# RTC-Module.net
KiCad netlist of a schematic drawn in EAGLE
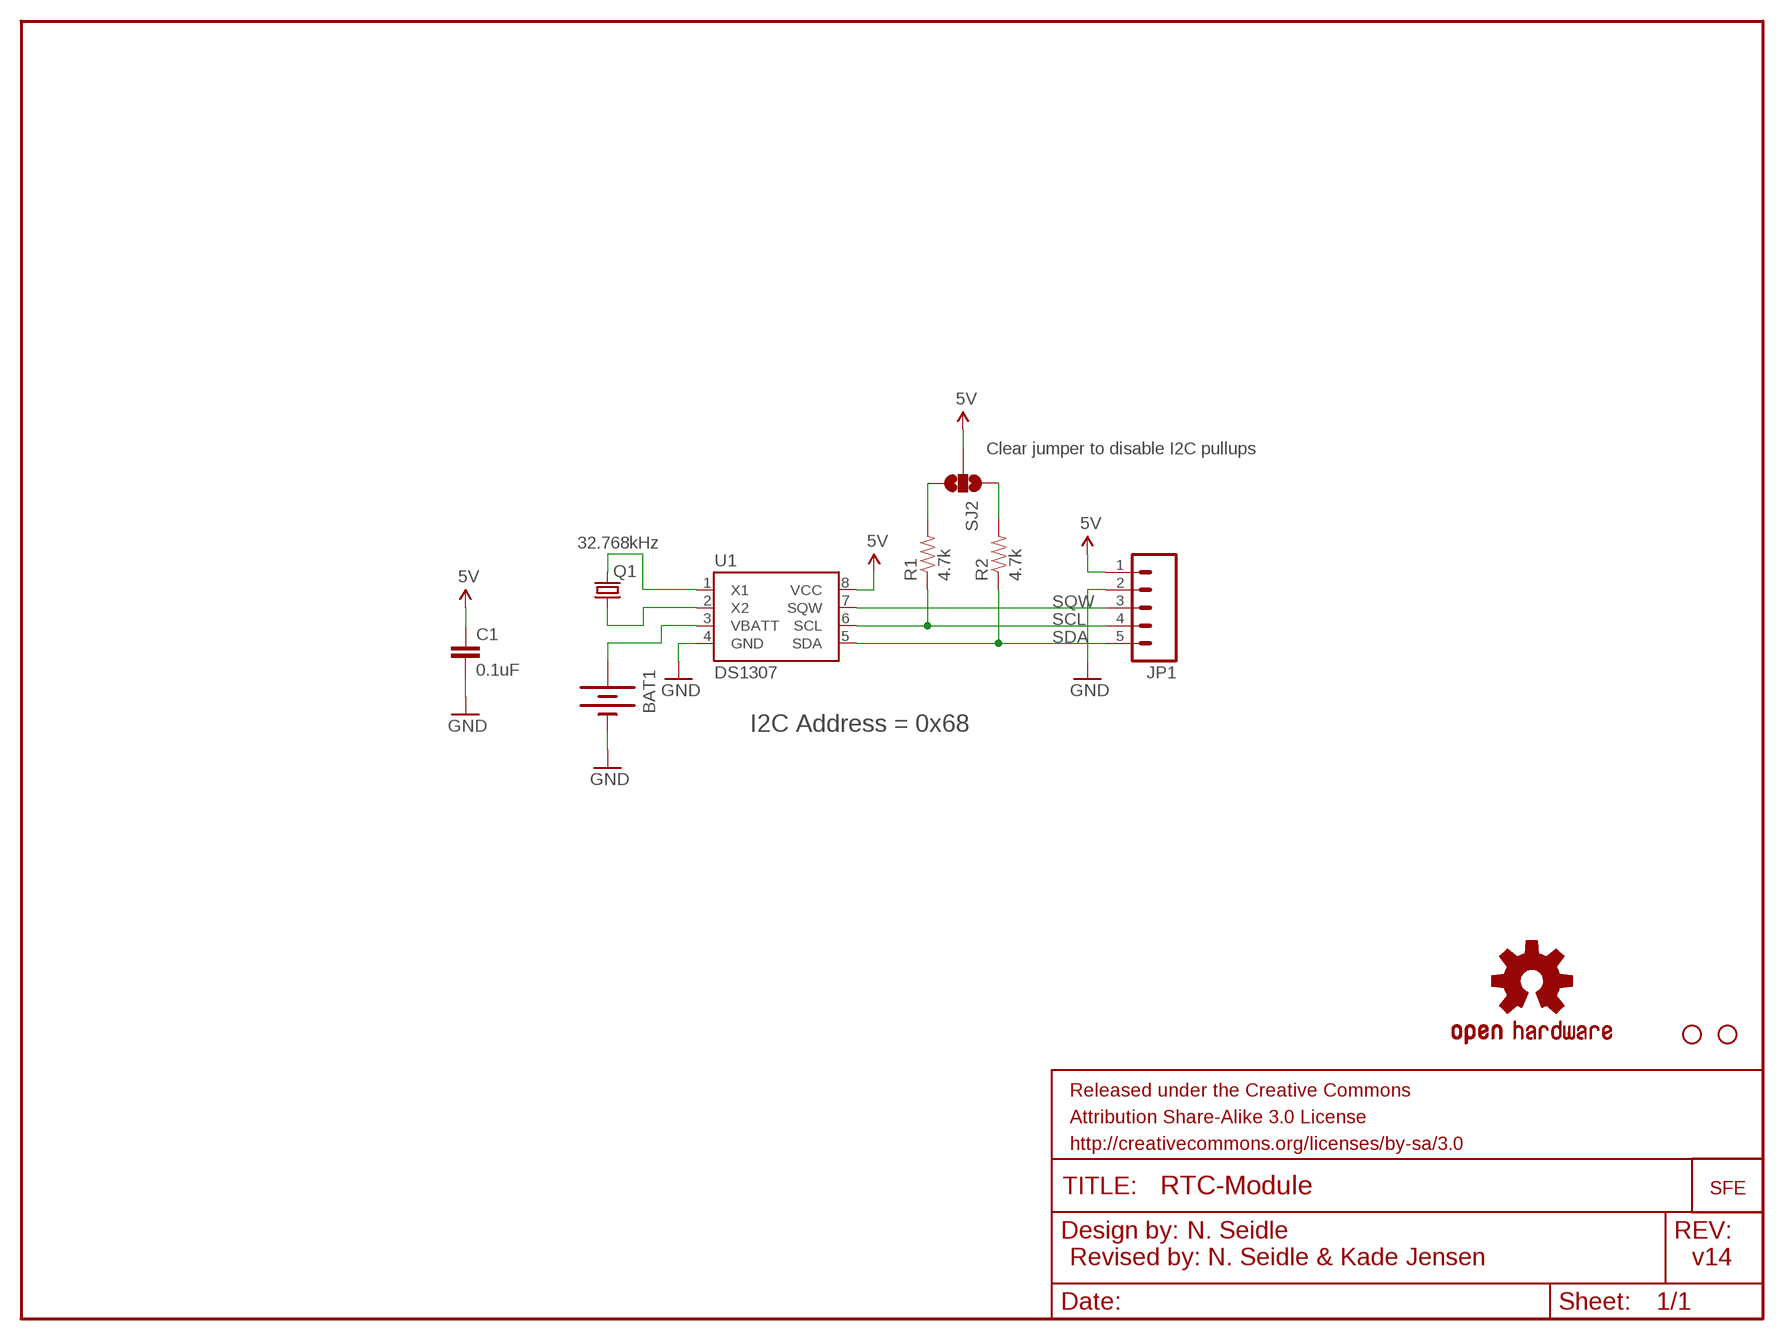
[diagram p0: schematic, sheet 1]

(export (version "E")
  (design (tool "Eeschema 10.0.6"))
  (components
    (comp (ref "BAT1")
      (value "BATTERY12PTH")
      (footprint "eagle-import:BATTCON_12MM_PTH")
      (libsource (lib "eagle-import") (part "BATTERY12PTH"))
    )
    (comp (ref "C1")
      (value "0.1uF")
      (footprint "eagle-import:0603-CAP")
      (libsource (lib "eagle-import") (part "0.1UF-25V(+80/-20%)(0603)"))
    )
    (comp (ref "FRAME2")
      (value "FRAME-LETTER")
      (footprint "eagle-import:CREATIVE_COMMONS")
      (libsource (lib "eagle-import") (part "FRAME-LETTER"))
    )
    (comp (ref "JP1")
      (value "M05PTH")
      (footprint "eagle-import:1X05")
      (libsource (lib "eagle-import") (part "M05PTH"))
    )
    (comp (ref "LOGO1")
      (value "OSHW-LOGOS")
      (footprint "eagle-import:OSHW-LOGO-S")
      (libsource (lib "eagle-import") (part "OSHW-LOGOS"))
    )
    (comp (ref "Q1")
      (value "32.768kHz")
      (footprint "eagle-import:CRYSTAL-32KHZ-SMD")
      (libsource (lib "eagle-import") (part "CRYSTAL32-SMD"))
    )
    (comp (ref "R1")
      (value "4.7k")
      (footprint "eagle-import:0603")
      (libsource (lib "eagle-import") (part "4.7KOHM1/10W1%(0603)"))
    )
    (comp (ref "R2")
      (value "4.7k")
      (footprint "eagle-import:0603")
      (libsource (lib "eagle-import") (part "4.7KOHM1/10W1%(0603)"))
    )
    (comp (ref "SJ2")
      (value "SOLDERJUMPER_2WAYPASTE1&2&3")
      (footprint "eagle-import:SJ_3_PASTE1&2&3")
      (libsource (lib "eagle-import") (part "SOLDERJUMPER_2WAYPASTE1&2&3"))
    )
    (comp (ref "U$2")
      (value "LOGO-SFESK")
      (footprint "eagle-import:SFE-LOGO-FLAME")
      (libsource (lib "eagle-import") (part "LOGO-SFESK"))
    )
    (comp (ref "U$6")
      (value "STAND-OFF")
      (footprint "eagle-import:STAND-OFF")
      (libsource (lib "eagle-import") (part "STAND-OFF"))
    )
    (comp (ref "U$7")
      (value "STAND-OFF")
      (footprint "eagle-import:STAND-OFF")
      (libsource (lib "eagle-import") (part "STAND-OFF"))
    )
    (comp (ref "U1")
      (value "DS1307")
      (footprint "eagle-import:SO08-TIGHT")
      (libsource (lib "eagle-import") (part "DS1307SO8-TIGHT"))
    )
  )
  (nets
    (net (code "1") (name "/SCL") (class "Default")
      (node (ref "JP1") (pin "4") (pinfunction "4_4") (pintype "passive"))
      (node (ref "R1") (pin "1") (pinfunction "1_1") (pintype "passive"))
      (node (ref "U1") (pin "6") (pinfunction "SCL_6") (pintype "bidirectional"))
    )
    (net (code "2") (name "/SDA") (class "Default")
      (node (ref "JP1") (pin "5") (pinfunction "5_5") (pintype "passive"))
      (node (ref "R2") (pin "1") (pinfunction "1_1") (pintype "passive"))
      (node (ref "U1") (pin "5") (pinfunction "SDA_5") (pintype "bidirectional"))
    )
    (net (code "3") (name "/SQW") (class "Default")
      (node (ref "JP1") (pin "3") (pinfunction "3_3") (pintype "passive"))
      (node (ref "U1") (pin "7") (pinfunction "SQW_7") (pintype "bidirectional"))
    )
    (net (code "4") (name "5V") (class "Default")
      (node (ref "C1") (pin "1") (pinfunction "1_1") (pintype "passive"))
      (node (ref "JP1") (pin "1") (pinfunction "1_1") (pintype "passive"))
      (node (ref "SJ2") (pin "2") (pinfunction "2_2") (pintype "passive"))
      (node (ref "U1") (pin "8") (pinfunction "VCC_8") (pintype "bidirectional"))
    )
    (net (code "5") (name "GND") (class "Default")
      (node (ref "BAT1") (pin "GND") (pinfunction "-_GND") (pintype "power_in"))
      (node (ref "C1") (pin "2") (pinfunction "2_2") (pintype "passive"))
      (node (ref "JP1") (pin "2") (pinfunction "2_2") (pintype "passive"))
      (node (ref "U1") (pin "4") (pinfunction "GND_4") (pintype "bidirectional"))
    )
    (net (code "6") (name "Net-(BAT1-+)") (class "Default")
      (node (ref "BAT1") (pin "VCC@1") (pinfunction "+_VCC@1") (pintype "power_in"))
      (node (ref "U1") (pin "3") (pinfunction "VBATT_3") (pintype "bidirectional"))
    )
    (net (code "7") (name "Net-(Q1-1)") (class "Default")
      (node (ref "Q1") (pin "X1") (pinfunction "1_X1") (pintype "passive"))
      (node (ref "U1") (pin "2") (pinfunction "X2_2") (pintype "bidirectional"))
    )
    (net (code "8") (name "Net-(Q1-2)") (class "Default")
      (node (ref "Q1") (pin "X2") (pinfunction "2_X2") (pintype "passive"))
      (node (ref "U1") (pin "1") (pinfunction "X1_1") (pintype "bidirectional"))
    )
    (net (code "9") (name "Net-(R1-Pad2)") (class "Default")
      (node (ref "R1") (pin "2") (pinfunction "2_2") (pintype "passive"))
      (node (ref "SJ2") (pin "3") (pinfunction "3_3") (pintype "passive"))
    )
    (net (code "10") (name "Net-(R2-Pad2)") (class "Default")
      (node (ref "R2") (pin "2") (pinfunction "2_2") (pintype "passive"))
      (node (ref "SJ2") (pin "1") (pinfunction "1_1") (pintype "passive"))
    )
  )
)
